# lcd_carrier.net
KiCad netlist of a schematic drawn in EAGLE
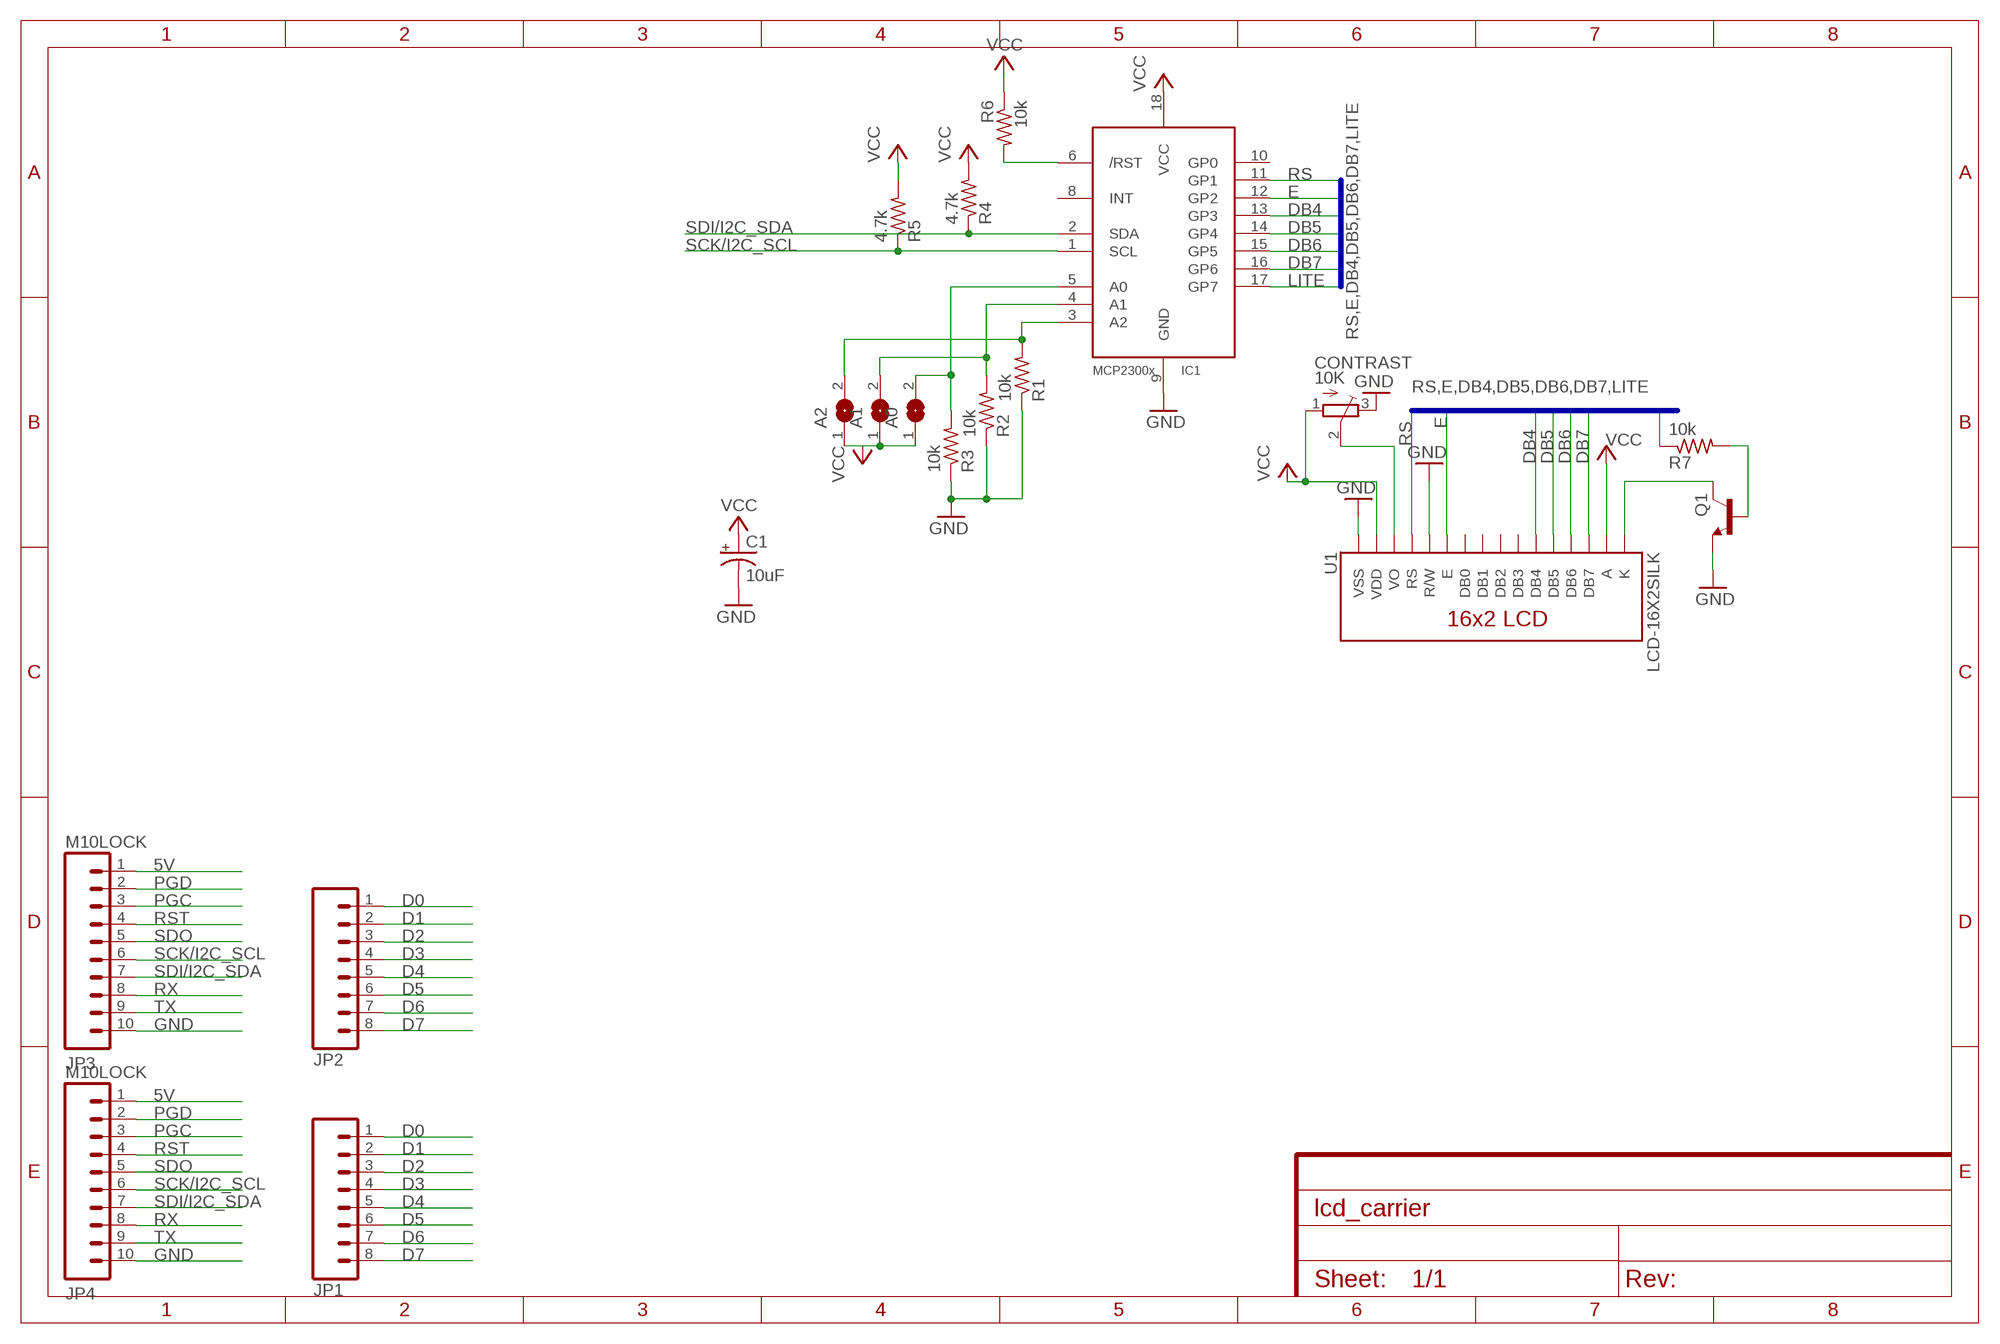
[diagram p0: schematic, sheet 1]

(export (version "E")
  (design (tool "Eeschema 10.0.6"))
  (components
    (comp (ref "A0") (value "SJ") (footprint "eagle-import:SJ") (libsource (lib "eagle-import") (part "SJ")))
    (comp (ref "A1") (value "SJ") (footprint "eagle-import:SJ") (libsource (lib "eagle-import") (part "SJ")))
    (comp (ref "A2") (value "SJ") (footprint "eagle-import:SJ") (libsource (lib "eagle-import") (part "SJ")))
    (comp (ref "C1")
      (value "10uF")
      (footprint "eagle-import:A_3216-18R")
      (libsource (lib "eagle-import") (part "CPOL-USA/3216-18R"))
    )
    (comp (ref "CONTRAST")
      (value "10K")
      (footprint "eagle-import:TC33X")
      (libsource (lib "eagle-import") (part "TRIMPOTTC33X"))
    )
    (comp (ref "IC1")
      (value "MCP2300X/SO")
      (footprint "eagle-import:SO18W")
      (libsource (lib "eagle-import") (part "MCP2300X/SO"))
    )
    (comp (ref "JP1")
      (value "M08LOCK")
      (footprint "eagle-import:1X08_LOCK")
      (libsource (lib "eagle-import") (part "M08LOCK"))
    )
    (comp (ref "JP2")
      (value "M08LOCK")
      (footprint "eagle-import:1X08_LOCK")
      (libsource (lib "eagle-import") (part "M08LOCK"))
    )
    (comp (ref "JP3")
      (value "M10LOCK")
      (footprint "eagle-import:1X10_LOCK")
      (libsource (lib "eagle-import") (part "M10LOCK"))
    )
    (comp (ref "JP4")
      (value "M10LOCK")
      (footprint "eagle-import:1X10_LOCK")
      (libsource (lib "eagle-import") (part "M10LOCK"))
    )
    (comp (ref "Q1")
      (value "MMBT2222ALT1-NPN-SOT23-BEC")
      (footprint "eagle-import:SOT23-BEC")
      (libsource (lib "eagle-import") (part "-NPN-SOT23-BECMMBT2222ALT1"))
    )
    (comp (ref "R1")
      (value "10k")
      (footprint "eagle-import:R0805")
      (libsource (lib "eagle-import") (part "R-US_R0805"))
    )
    (comp (ref "R2")
      (value "10k")
      (footprint "eagle-import:R0805")
      (libsource (lib "eagle-import") (part "R-US_R0805"))
    )
    (comp (ref "R3")
      (value "10k")
      (footprint "eagle-import:R0805")
      (libsource (lib "eagle-import") (part "R-US_R0805"))
    )
    (comp (ref "R4")
      (value "4.7k")
      (footprint "eagle-import:R0805")
      (libsource (lib "eagle-import") (part "R-US_R0805"))
    )
    (comp (ref "R5")
      (value "4.7k")
      (footprint "eagle-import:R0805")
      (libsource (lib "eagle-import") (part "R-US_R0805"))
    )
    (comp (ref "R6")
      (value "10k")
      (footprint "eagle-import:R0805")
      (libsource (lib "eagle-import") (part "R-US_R0805"))
    )
    (comp (ref "R7")
      (value "10k")
      (footprint "eagle-import:R0805")
      (libsource (lib "eagle-import") (part "R-US_R0805"))
    )
    (comp (ref "U1")
      (value "LCD-16X2SILK")
      (footprint "eagle-import:LCD-16X2")
      (libsource (lib "eagle-import") (part "LCD-16X2SILK"))
    )
  )
  (nets
    (net (code "1") (name "/5V") (class "Default")
      (node (ref "JP3") (pin "1") (pinfunction "1_1") (pintype "passive"))
      (node (ref "JP4") (pin "1") (pinfunction "1_1") (pintype "passive"))
    )
    (net (code "2") (name "/D0") (class "Default")
      (node (ref "JP1") (pin "1") (pinfunction "1_1") (pintype "passive"))
      (node (ref "JP2") (pin "1") (pinfunction "1_1") (pintype "passive"))
    )
    (net (code "3") (name "/D1") (class "Default")
      (node (ref "JP1") (pin "2") (pinfunction "2_2") (pintype "passive"))
      (node (ref "JP2") (pin "2") (pinfunction "2_2") (pintype "passive"))
    )
    (net (code "4") (name "/D2") (class "Default")
      (node (ref "JP1") (pin "3") (pinfunction "3_3") (pintype "passive"))
      (node (ref "JP2") (pin "3") (pinfunction "3_3") (pintype "passive"))
    )
    (net (code "5") (name "/D3") (class "Default")
      (node (ref "JP1") (pin "4") (pinfunction "4_4") (pintype "passive"))
      (node (ref "JP2") (pin "4") (pinfunction "4_4") (pintype "passive"))
    )
    (net (code "6") (name "/D4") (class "Default")
      (node (ref "JP1") (pin "5") (pinfunction "5_5") (pintype "passive"))
      (node (ref "JP2") (pin "5") (pinfunction "5_5") (pintype "passive"))
    )
    (net (code "7") (name "/D5") (class "Default")
      (node (ref "JP1") (pin "6") (pinfunction "6_6") (pintype "passive"))
      (node (ref "JP2") (pin "6") (pinfunction "6_6") (pintype "passive"))
    )
    (net (code "8") (name "/D6") (class "Default")
      (node (ref "JP1") (pin "7") (pinfunction "7_7") (pintype "passive"))
      (node (ref "JP2") (pin "7") (pinfunction "7_7") (pintype "passive"))
    )
    (net (code "9") (name "/D7") (class "Default")
      (node (ref "JP1") (pin "8") (pinfunction "8_8") (pintype "passive"))
      (node (ref "JP2") (pin "8") (pinfunction "8_8") (pintype "passive"))
    )
    (net (code "10") (name "/DB4") (class "Default")
      (node (ref "IC1") (pin "13") (pinfunction "GP3_13") (pintype "bidirectional"))
      (node (ref "U1") (pin "11") (pinfunction "DB4_11") (pintype "bidirectional"))
    )
    (net (code "11") (name "/DB5") (class "Default")
      (node (ref "IC1") (pin "14") (pinfunction "GP4_14") (pintype "bidirectional"))
      (node (ref "U1") (pin "12") (pinfunction "DB5_12") (pintype "bidirectional"))
    )
    (net (code "12") (name "/DB6") (class "Default")
      (node (ref "IC1") (pin "15") (pinfunction "GP5_15") (pintype "bidirectional"))
      (node (ref "U1") (pin "13") (pinfunction "DB6_13") (pintype "bidirectional"))
    )
    (net (code "13") (name "/DB7") (class "Default")
      (node (ref "IC1") (pin "16") (pinfunction "GP6_16") (pintype "bidirectional"))
      (node (ref "U1") (pin "14") (pinfunction "DB7_14") (pintype "bidirectional"))
    )
    (net (code "14") (name "/E") (class "Default")
      (node (ref "IC1") (pin "12") (pinfunction "GP2_12") (pintype "bidirectional"))
      (node (ref "U1") (pin "6") (pinfunction "E_6") (pintype "input"))
    )
    (net (code "15") (name "/LITE") (class "Default")
      (node (ref "IC1") (pin "17") (pinfunction "GP7_17") (pintype "bidirectional"))
      (node (ref "R7") (pin "1") (pinfunction "1_1") (pintype "passive"))
    )
    (net (code "16") (name "/PGC") (class "Default")
      (node (ref "JP3") (pin "3") (pinfunction "3_3") (pintype "passive"))
      (node (ref "JP4") (pin "3") (pinfunction "3_3") (pintype "passive"))
    )
    (net (code "17") (name "/PGD") (class "Default")
      (node (ref "JP3") (pin "2") (pinfunction "2_2") (pintype "passive"))
      (node (ref "JP4") (pin "2") (pinfunction "2_2") (pintype "passive"))
    )
    (net (code "18") (name "/RS") (class "Default")
      (node (ref "IC1") (pin "11") (pinfunction "GP1_11") (pintype "bidirectional"))
      (node (ref "U1") (pin "4") (pinfunction "RS_4") (pintype "input"))
    )
    (net (code "19") (name "/RST") (class "Default")
      (node (ref "JP3") (pin "4") (pinfunction "4_4") (pintype "passive"))
      (node (ref "JP4") (pin "4") (pinfunction "4_4") (pintype "passive"))
    )
    (net (code "20") (name "/RX") (class "Default")
      (node (ref "JP3") (pin "8") (pinfunction "8_8") (pintype "passive"))
      (node (ref "JP4") (pin "8") (pinfunction "8_8") (pintype "passive"))
    )
    (net (code "21") (name "/SCK{slash}I2C_SCL") (class "Default")
      (node (ref "IC1") (pin "1") (pinfunction "SCL_1") (pintype "bidirectional"))
      (node (ref "JP3") (pin "6") (pinfunction "6_6") (pintype "passive"))
      (node (ref "JP4") (pin "6") (pinfunction "6_6") (pintype "passive"))
      (node (ref "R5") (pin "1") (pinfunction "1_1") (pintype "passive"))
    )
    (net (code "22") (name "/SDI{slash}I2C_SDA") (class "Default")
      (node (ref "IC1") (pin "2") (pinfunction "SDA_2") (pintype "bidirectional"))
      (node (ref "JP3") (pin "7") (pinfunction "7_7") (pintype "passive"))
      (node (ref "JP4") (pin "7") (pinfunction "7_7") (pintype "passive"))
      (node (ref "R4") (pin "1") (pinfunction "1_1") (pintype "passive"))
    )
    (net (code "23") (name "/SDO") (class "Default")
      (node (ref "JP3") (pin "5") (pinfunction "5_5") (pintype "passive"))
      (node (ref "JP4") (pin "5") (pinfunction "5_5") (pintype "passive"))
    )
    (net (code "24") (name "/TX") (class "Default")
      (node (ref "JP3") (pin "9") (pinfunction "9_9") (pintype "passive"))
      (node (ref "JP4") (pin "9") (pinfunction "9_9") (pintype "passive"))
    )
    (net (code "26") (name "GND") (class "Default")
      (node (ref "C1") (pin "-") (pinfunction "-_-") (pintype "passive"))
      (node (ref "CONTRAST") (pin "3") (pinfunction "E_3") (pintype "passive"))
      (node (ref "IC1") (pin "9") (pinfunction "GND_9") (pintype "power_in"))
      (node (ref "JP3") (pin "10") (pinfunction "10_10") (pintype "passive"))
      (node (ref "JP4") (pin "10") (pinfunction "10_10") (pintype "passive"))
      (node (ref "Q1") (pin "E") (pinfunction "E_E") (pintype "passive"))
      (node (ref "R1") (pin "1") (pinfunction "1_1") (pintype "passive"))
      (node (ref "R2") (pin "1") (pinfunction "1_1") (pintype "passive"))
      (node (ref "R3") (pin "1") (pinfunction "1_1") (pintype "passive"))
      (node (ref "U1") (pin "1") (pinfunction "VSS_1") (pintype "power_in"))
      (node (ref "U1") (pin "5") (pinfunction "R/W_5") (pintype "input"))
    )
    (net (code "27") (name "Net-(CONTRAST-S)") (class "Default")
      (node (ref "CONTRAST") (pin "2") (pinfunction "S_2") (pintype "passive"))
      (node (ref "U1") (pin "3") (pinfunction "VO_3") (pintype "bidirectional"))
    )
    (net (code "28") (name "Net-(IC1-A0)") (class "Default")
      (node (ref "A0") (pin "2") (pinfunction "2_2") (pintype "passive"))
      (node (ref "IC1") (pin "5") (pinfunction "A0_5") (pintype "input"))
      (node (ref "R3") (pin "2") (pinfunction "2_2") (pintype "passive"))
    )
    (net (code "29") (name "Net-(IC1-A1)") (class "Default")
      (node (ref "A1") (pin "2") (pinfunction "2_2") (pintype "passive"))
      (node (ref "IC1") (pin "4") (pinfunction "A1_4") (pintype "input"))
      (node (ref "R2") (pin "2") (pinfunction "2_2") (pintype "passive"))
    )
    (net (code "30") (name "Net-(IC1-A2)") (class "Default")
      (node (ref "A2") (pin "2") (pinfunction "2_2") (pintype "passive"))
      (node (ref "IC1") (pin "3") (pinfunction "A2_3") (pintype "input"))
      (node (ref "R1") (pin "2") (pinfunction "2_2") (pintype "passive"))
    )
    (net (code "31") (name "Net-(IC1-{slash}RST)") (class "Default")
      (node (ref "IC1") (pin "6") (pinfunction "/RST_6") (pintype "input"))
      (node (ref "R6") (pin "2") (pinfunction "2_2") (pintype "passive"))
    )
    (net (code "32") (name "Net-(Q1-PadB)") (class "Default")
      (node (ref "Q1") (pin "B") (pinfunction "B_B") (pintype "passive"))
      (node (ref "R7") (pin "2") (pinfunction "2_2") (pintype "passive"))
    )
    (net (code "33") (name "Net-(U1-K)") (class "Default")
      (node (ref "Q1") (pin "C") (pinfunction "C_C") (pintype "passive"))
      (node (ref "U1") (pin "16") (pinfunction "K_16") (pintype "power_in"))
    )
    (net (code "34") (name "VCC") (class "Default")
      (node (ref "A0") (pin "1") (pinfunction "1_1") (pintype "passive"))
      (node (ref "A1") (pin "1") (pinfunction "1_1") (pintype "passive"))
      (node (ref "A2") (pin "1") (pinfunction "1_1") (pintype "passive"))
      (node (ref "C1") (pin "+") (pinfunction "+_+") (pintype "passive"))
      (node (ref "CONTRAST") (pin "1") (pinfunction "A_1") (pintype "passive"))
      (node (ref "IC1") (pin "18") (pinfunction "VCC_18") (pintype "power_in"))
      (node (ref "R4") (pin "2") (pinfunction "2_2") (pintype "passive"))
      (node (ref "R5") (pin "2") (pinfunction "2_2") (pintype "passive"))
      (node (ref "R6") (pin "1") (pinfunction "1_1") (pintype "passive"))
      (node (ref "U1") (pin "15") (pinfunction "A_15") (pintype "power_in"))
      (node (ref "U1") (pin "2") (pinfunction "VDD_2") (pintype "power_in"))
    )
    (net (code "35") (name "unconnected-(IC1-GP0-Pad10)") (class "Default")
      (node (ref "IC1") (pin "10") (pinfunction "GP0_10") (pintype "bidirectional"))
    )
    (net (code "36") (name "unconnected-(IC1-INT-Pad8)") (class "Default")
      (node (ref "IC1") (pin "8") (pinfunction "INT_8") (pintype "output"))
    )
    (net (code "37") (name "unconnected-(U1-DB0-Pad7)") (class "Default")
      (node (ref "U1") (pin "7") (pinfunction "DB0_7") (pintype "bidirectional"))
    )
    (net (code "38") (name "unconnected-(U1-DB1-Pad8)") (class "Default")
      (node (ref "U1") (pin "8") (pinfunction "DB1_8") (pintype "bidirectional"))
    )
    (net (code "39") (name "unconnected-(U1-DB2-Pad9)") (class "Default")
      (node (ref "U1") (pin "9") (pinfunction "DB2_9") (pintype "bidirectional"))
    )
    (net (code "40") (name "unconnected-(U1-DB3-Pad10)") (class "Default")
      (node (ref "U1") (pin "10") (pinfunction "DB3_10") (pintype "bidirectional"))
    )
  )
)
